# vfd_dclink.net
KiCad netlist of a schematic drawn in EAGLE
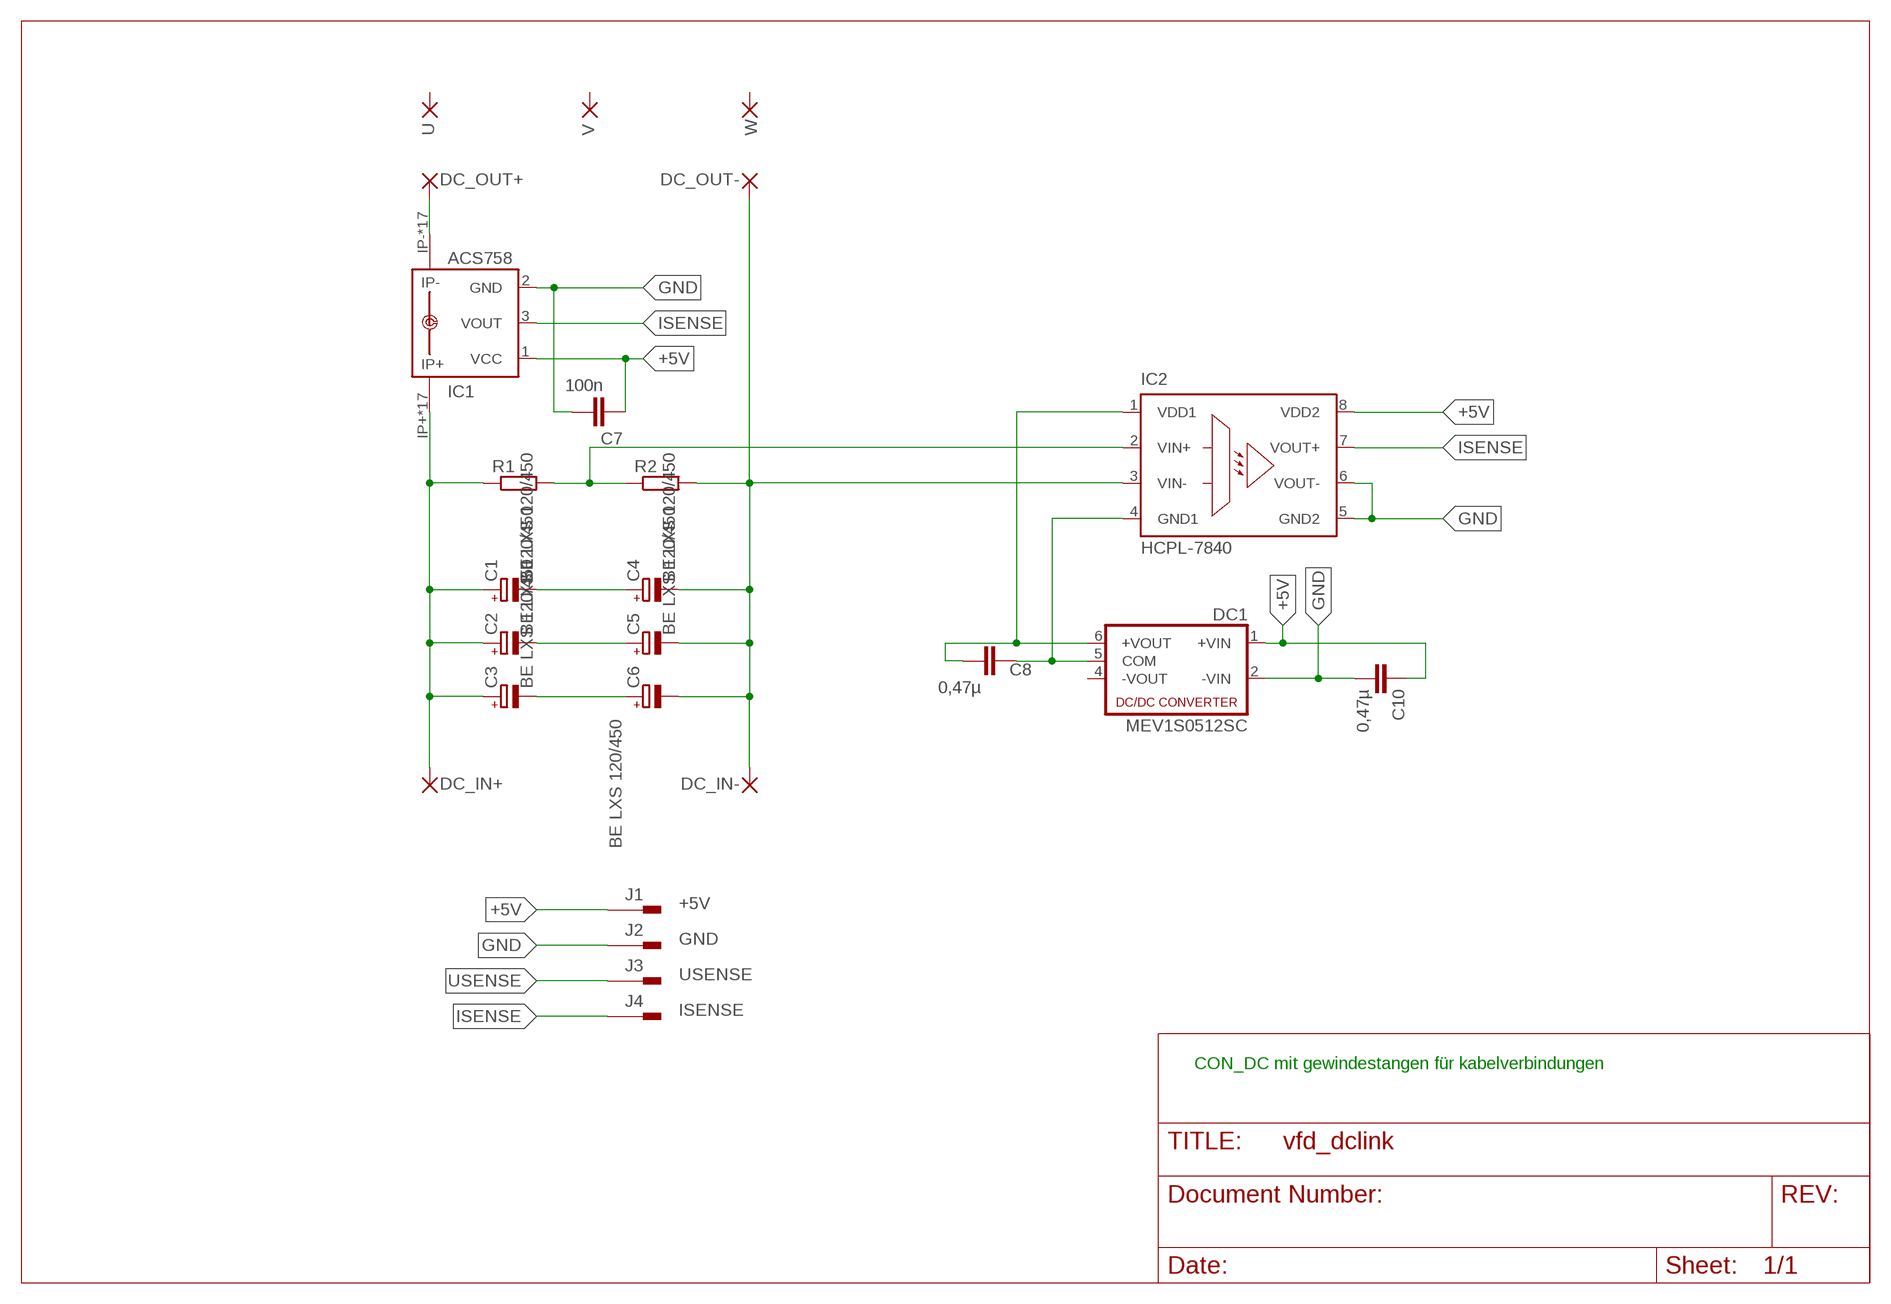
[diagram p0: schematic, sheet 1]

(export (version "E")
  (design (tool "Eeschema 10.0.6"))
  (components
    (comp (ref "C1")
      (value "BE LXS 120/450")
      (footprint "eagle-import:EB25D")
      (libsource (lib "eagle-import") (part "CPOL-EUE10-25"))
    )
    (comp (ref "C2")
      (value "BE LXS 120/450")
      (footprint "eagle-import:EB25D")
      (libsource (lib "eagle-import") (part "CPOL-EUE10-25"))
    )
    (comp (ref "C3")
      (value "BE LXS 120/450")
      (footprint "eagle-import:EB25D")
      (libsource (lib "eagle-import") (part "CPOL-EUE10-25"))
    )
    (comp (ref "C4")
      (value "BE LXS 120/450")
      (footprint "eagle-import:EB25D")
      (libsource (lib "eagle-import") (part "CPOL-EUE10-25"))
    )
    (comp (ref "C5")
      (value "BE LXS 120/450")
      (footprint "eagle-import:EB25D")
      (libsource (lib "eagle-import") (part "CPOL-EUE10-25"))
    )
    (comp (ref "C6")
      (value "BE LXS 120/450")
      (footprint "eagle-import:EB25D")
      (libsource (lib "eagle-import") (part "CPOL-EUE10-25"))
    )
    (comp (ref "C7")
      (value "100n")
      (footprint "eagle-import:C025-030X050")
      (libsource (lib "eagle-import") (part "C-EU025-030X050"))
    )
    (comp (ref "C8")
      (value "0,47µ")
      (footprint "eagle-import:C025-030X050")
      (libsource (lib "eagle-import") (part "C-EU025-030X050"))
    )
    (comp (ref "C10")
      (value "0,47µ")
      (footprint "eagle-import:C025-030X050")
      (libsource (lib "eagle-import") (part "C-EU025-030X050"))
    )
    (comp (ref "DC1")
      (value "MEV1S0512SC")
      (footprint "eagle-import:NMA")
      (fields (field (name "MF") "C & D TECHNOLOGIES, INC") (field (name "MPN") "NMA0515SC"))
      (libsource (lib "eagle-import") (part "NMA"))
    )
    (comp (ref "DC_IN+")
      (value "3,81/1,4")
      (footprint "eagle-import:3,81_1,4")
      (libsource (lib "eagle-import") (part "3,81/1,4"))
    )
    (comp (ref "DC_IN-")
      (value "3,81/1,4")
      (footprint "eagle-import:3,81_1,4")
      (libsource (lib "eagle-import") (part "3,81/1,4"))
    )
    (comp (ref "DC_OUT+")
      (value "3,81/1,4")
      (footprint "eagle-import:3,81_1,4")
      (libsource (lib "eagle-import") (part "3,81/1,4"))
    )
    (comp (ref "DC_OUT-")
      (value "3,81/1,4")
      (footprint "eagle-import:3,81_1,4")
      (libsource (lib "eagle-import") (part "3,81/1,4"))
    )
    (comp (ref "IC1")
      (value "ACS758")
      (footprint "eagle-import:CB-PFF")
      (fields (field (name "MPN") "ACS758ECB-200B-PFF-T"))
      (libsource (lib "eagle-import") (part "ACS758ECB-200B-PFF-T"))
    )
    (comp (ref "IC2")
      (value "HCPL-7840")
      (footprint "eagle-import:DIL08")
      (fields (field (name "MPN") "HCPL-7800A#500"))
      (libsource (lib "eagle-import") (part "HCPL-7800"))
    )
    (comp (ref "J1")
      (value "+5V")
      (footprint "eagle-import:F061.080")
      (libsource (lib "eagle-import") (part "PIN2F061.080"))
    )
    (comp (ref "J2")
      (value "GND")
      (footprint "eagle-import:F061.080")
      (libsource (lib "eagle-import") (part "PIN2F061.080"))
    )
    (comp (ref "J3")
      (value "USENSE")
      (footprint "eagle-import:F061.080")
      (libsource (lib "eagle-import") (part "PIN2F061.080"))
    )
    (comp (ref "J4")
      (value "ISENSE")
      (footprint "eagle-import:F061.080")
      (libsource (lib "eagle-import") (part "PIN2F061.080"))
    )
    (comp (ref "R1")
      (value "R-EU_0204/5")
      (footprint "eagle-import:0204_5")
      (libsource (lib "eagle-import") (part "R-EU_0204/5"))
    )
    (comp (ref "R2")
      (value "R-EU_0204/5")
      (footprint "eagle-import:0204_5")
      (libsource (lib "eagle-import") (part "R-EU_0204/5"))
    )
    (comp (ref "U")
      (value "3,81/1,4")
      (footprint "eagle-import:3,81_1,4")
      (libsource (lib "eagle-import") (part "3,81/1,4"))
    )
    (comp (ref "V")
      (value "3,81/1,4")
      (footprint "eagle-import:3,81_1,4")
      (libsource (lib "eagle-import") (part "3,81/1,4"))
    )
    (comp (ref "W")
      (value "3,81/1,4")
      (footprint "eagle-import:3,81_1,4")
      (libsource (lib "eagle-import") (part "3,81/1,4"))
    )
  )
  (nets
    (net (code "1") (name "+5V") (class "Default")
      (node (ref "C10") (pin "1") (pinfunction "1_1") (pintype "passive"))
      (node (ref "C7") (pin "2") (pinfunction "2_2") (pintype "passive"))
      (node (ref "DC1") (pin "1") (pinfunction "+VIN_1") (pintype "passive"))
      (node (ref "IC1") (pin "1") (pinfunction "VCC_1") (pintype "power_in"))
      (node (ref "IC2") (pin "8") (pinfunction "VDD2_8") (pintype "power_in"))
      (node (ref "J1") (pin "1A") (pinfunction "1_1A") (pintype "passive"))
      (node (ref "J1") (pin "1B") (pinfunction "1_1B") (pintype "passive"))
    )
    (net (code "2") (name "GND") (class "Default")
      (node (ref "C10") (pin "2") (pinfunction "2_2") (pintype "passive"))
      (node (ref "C7") (pin "1") (pinfunction "1_1") (pintype "passive"))
      (node (ref "DC1") (pin "2") (pinfunction "-VIN_2") (pintype "passive"))
      (node (ref "IC1") (pin "2") (pinfunction "GND_2") (pintype "power_in"))
      (node (ref "IC2") (pin "5") (pinfunction "GND2_5") (pintype "power_in"))
      (node (ref "IC2") (pin "6") (pinfunction "VOUT-_6") (pintype "power_in"))
      (node (ref "J2") (pin "1A") (pinfunction "1_1A") (pintype "passive"))
      (node (ref "J2") (pin "1B") (pinfunction "1_1B") (pintype "passive"))
    )
    (net (code "3") (name "ISENSE") (class "Default")
      (node (ref "IC1") (pin "3") (pinfunction "VOUT_3") (pintype "output"))
      (node (ref "IC2") (pin "7") (pinfunction "VOUT+_7") (pintype "power_in"))
      (node (ref "J4") (pin "1A") (pinfunction "1_1A") (pintype "passive"))
      (node (ref "J4") (pin "1B") (pinfunction "1_1B") (pintype "passive"))
    )
    (net (code "4") (name "Net-(C1-Pad-)") (class "Default")
      (node (ref "C1") (pin "-") (pinfunction "-_-") (pintype "passive"))
      (node (ref "C4") (pin "+") (pinfunction "+_+") (pintype "passive"))
    )
    (net (code "5") (name "Net-(C2-Pad-)") (class "Default")
      (node (ref "C2") (pin "-") (pinfunction "-_-") (pintype "passive"))
      (node (ref "C5") (pin "+") (pinfunction "+_+") (pintype "passive"))
    )
    (net (code "6") (name "Net-(C3-Pad-)") (class "Default")
      (node (ref "C3") (pin "-") (pinfunction "-_-") (pintype "passive"))
      (node (ref "C6") (pin "+") (pinfunction "+_+") (pintype "passive"))
    )
    (net (code "7") (name "Net-(DC1-+VOUT)") (class "Default")
      (node (ref "C8") (pin "2") (pinfunction "2_2") (pintype "passive"))
      (node (ref "DC1") (pin "6") (pinfunction "+VOUT_6") (pintype "passive"))
      (node (ref "IC2") (pin "1") (pinfunction "VDD1_1") (pintype "power_in"))
    )
    (net (code "8") (name "Net-(DC1-COM)") (class "Default")
      (node (ref "C8") (pin "1") (pinfunction "1_1") (pintype "passive"))
      (node (ref "DC1") (pin "5") (pinfunction "COM_5") (pintype "passive"))
      (node (ref "IC2") (pin "4") (pinfunction "GND1_4") (pintype "power_in"))
    )
    (net (code "9") (name "Net-(DC_IN+-P)") (class "Default")
      (node (ref "C1") (pin "+") (pinfunction "+_+") (pintype "passive"))
      (node (ref "C2") (pin "+") (pinfunction "+_+") (pintype "passive"))
      (node (ref "C3") (pin "+") (pinfunction "+_+") (pintype "passive"))
      (node (ref "DC_IN+") (pin "1") (pinfunction "P_1") (pintype "passive"))
      (node (ref "IC1") (pin "IP+") (pinfunction "IP+_IP+") (pintype "passive"))
      (node (ref "IC1") (pin "IP+@10") (pinfunction "IP+_IP+@10") (pintype "passive"))
      (node (ref "IC1") (pin "IP+@11") (pinfunction "IP+_IP+@11") (pintype "passive"))
      (node (ref "IC1") (pin "IP+@12") (pinfunction "IP+_IP+@12") (pintype "passive"))
      (node (ref "IC1") (pin "IP+@13") (pinfunction "IP+_IP+@13") (pintype "passive"))
      (node (ref "IC1") (pin "IP+@14") (pinfunction "IP+_IP+@14") (pintype "passive"))
      (node (ref "IC1") (pin "IP+@15") (pinfunction "IP+_IP+@15") (pintype "passive"))
      (node (ref "IC1") (pin "IP+@16") (pinfunction "IP+_IP+@16") (pintype "passive"))
      (node (ref "IC1") (pin "IP+@17") (pinfunction "IP+_IP+@17") (pintype "passive"))
      (node (ref "IC1") (pin "IP+@2") (pinfunction "IP+_IP+@2") (pintype "passive"))
      (node (ref "IC1") (pin "IP+@3") (pinfunction "IP+_IP+@3") (pintype "passive"))
      (node (ref "IC1") (pin "IP+@4") (pinfunction "IP+_IP+@4") (pintype "passive"))
      (node (ref "IC1") (pin "IP+@5") (pinfunction "IP+_IP+@5") (pintype "passive"))
      (node (ref "IC1") (pin "IP+@6") (pinfunction "IP+_IP+@6") (pintype "passive"))
      (node (ref "IC1") (pin "IP+@7") (pinfunction "IP+_IP+@7") (pintype "passive"))
      (node (ref "IC1") (pin "IP+@8") (pinfunction "IP+_IP+@8") (pintype "passive"))
      (node (ref "IC1") (pin "IP+@9") (pinfunction "IP+_IP+@9") (pintype "passive"))
      (node (ref "R1") (pin "1") (pinfunction "1_1") (pintype "passive"))
    )
    (net (code "10") (name "Net-(DC_IN--P)") (class "Default")
      (node (ref "C4") (pin "-") (pinfunction "-_-") (pintype "passive"))
      (node (ref "C5") (pin "-") (pinfunction "-_-") (pintype "passive"))
      (node (ref "C6") (pin "-") (pinfunction "-_-") (pintype "passive"))
      (node (ref "DC_IN-") (pin "1") (pinfunction "P_1") (pintype "passive"))
      (node (ref "DC_OUT-") (pin "1") (pinfunction "P_1") (pintype "passive"))
      (node (ref "IC2") (pin "3") (pinfunction "VIN-_3") (pintype "power_in"))
      (node (ref "R2") (pin "2") (pinfunction "2_2") (pintype "passive"))
    )
    (net (code "11") (name "Net-(DC_OUT+-P)") (class "Default")
      (node (ref "DC_OUT+") (pin "1") (pinfunction "P_1") (pintype "passive"))
      (node (ref "IC1") (pin "IP-") (pinfunction "IP-_IP-") (pintype "passive"))
      (node (ref "IC1") (pin "IP-@10") (pinfunction "IP-_IP-@10") (pintype "passive"))
      (node (ref "IC1") (pin "IP-@11") (pinfunction "IP-_IP-@11") (pintype "passive"))
      (node (ref "IC1") (pin "IP-@12") (pinfunction "IP-_IP-@12") (pintype "passive"))
      (node (ref "IC1") (pin "IP-@13") (pinfunction "IP-_IP-@13") (pintype "passive"))
      (node (ref "IC1") (pin "IP-@14") (pinfunction "IP-_IP-@14") (pintype "passive"))
      (node (ref "IC1") (pin "IP-@15") (pinfunction "IP-_IP-@15") (pintype "passive"))
      (node (ref "IC1") (pin "IP-@16") (pinfunction "IP-_IP-@16") (pintype "passive"))
      (node (ref "IC1") (pin "IP-@17") (pinfunction "IP-_IP-@17") (pintype "passive"))
      (node (ref "IC1") (pin "IP-@2") (pinfunction "IP-_IP-@2") (pintype "passive"))
      (node (ref "IC1") (pin "IP-@3") (pinfunction "IP-_IP-@3") (pintype "passive"))
      (node (ref "IC1") (pin "IP-@4") (pinfunction "IP-_IP-@4") (pintype "passive"))
      (node (ref "IC1") (pin "IP-@5") (pinfunction "IP-_IP-@5") (pintype "passive"))
      (node (ref "IC1") (pin "IP-@6") (pinfunction "IP-_IP-@6") (pintype "passive"))
      (node (ref "IC1") (pin "IP-@7") (pinfunction "IP-_IP-@7") (pintype "passive"))
      (node (ref "IC1") (pin "IP-@8") (pinfunction "IP-_IP-@8") (pintype "passive"))
      (node (ref "IC1") (pin "IP-@9") (pinfunction "IP-_IP-@9") (pintype "passive"))
    )
    (net (code "12") (name "Net-(IC2-VIN+)") (class "Default")
      (node (ref "IC2") (pin "2") (pinfunction "VIN+_2") (pintype "power_in"))
      (node (ref "R1") (pin "2") (pinfunction "2_2") (pintype "passive"))
      (node (ref "R2") (pin "1") (pinfunction "1_1") (pintype "passive"))
    )
    (net (code "13") (name "USENSE") (class "Default")
      (node (ref "J3") (pin "1A") (pinfunction "1_1A") (pintype "passive"))
      (node (ref "J3") (pin "1B") (pinfunction "1_1B") (pintype "passive"))
    )
    (net (code "14") (name "unconnected-(DC1--VOUT-Pad4)") (class "Default")
      (node (ref "DC1") (pin "4") (pinfunction "-VOUT_4") (pintype "passive"))
    )
    (net (code "15") (name "unconnected-(U-P-Pad1)") (class "Default")
      (node (ref "U") (pin "1") (pinfunction "P_1") (pintype "passive"))
    )
    (net (code "16") (name "unconnected-(V-P-Pad1)") (class "Default")
      (node (ref "V") (pin "1") (pinfunction "P_1") (pintype "passive"))
    )
    (net (code "17") (name "unconnected-(W-P-Pad1)") (class "Default")
      (node (ref "W") (pin "1") (pinfunction "P_1") (pintype "passive"))
    )
  )
)
